# Wifi_and_Tip_120.net
KiCad netlist of a schematic drawn in EAGLE
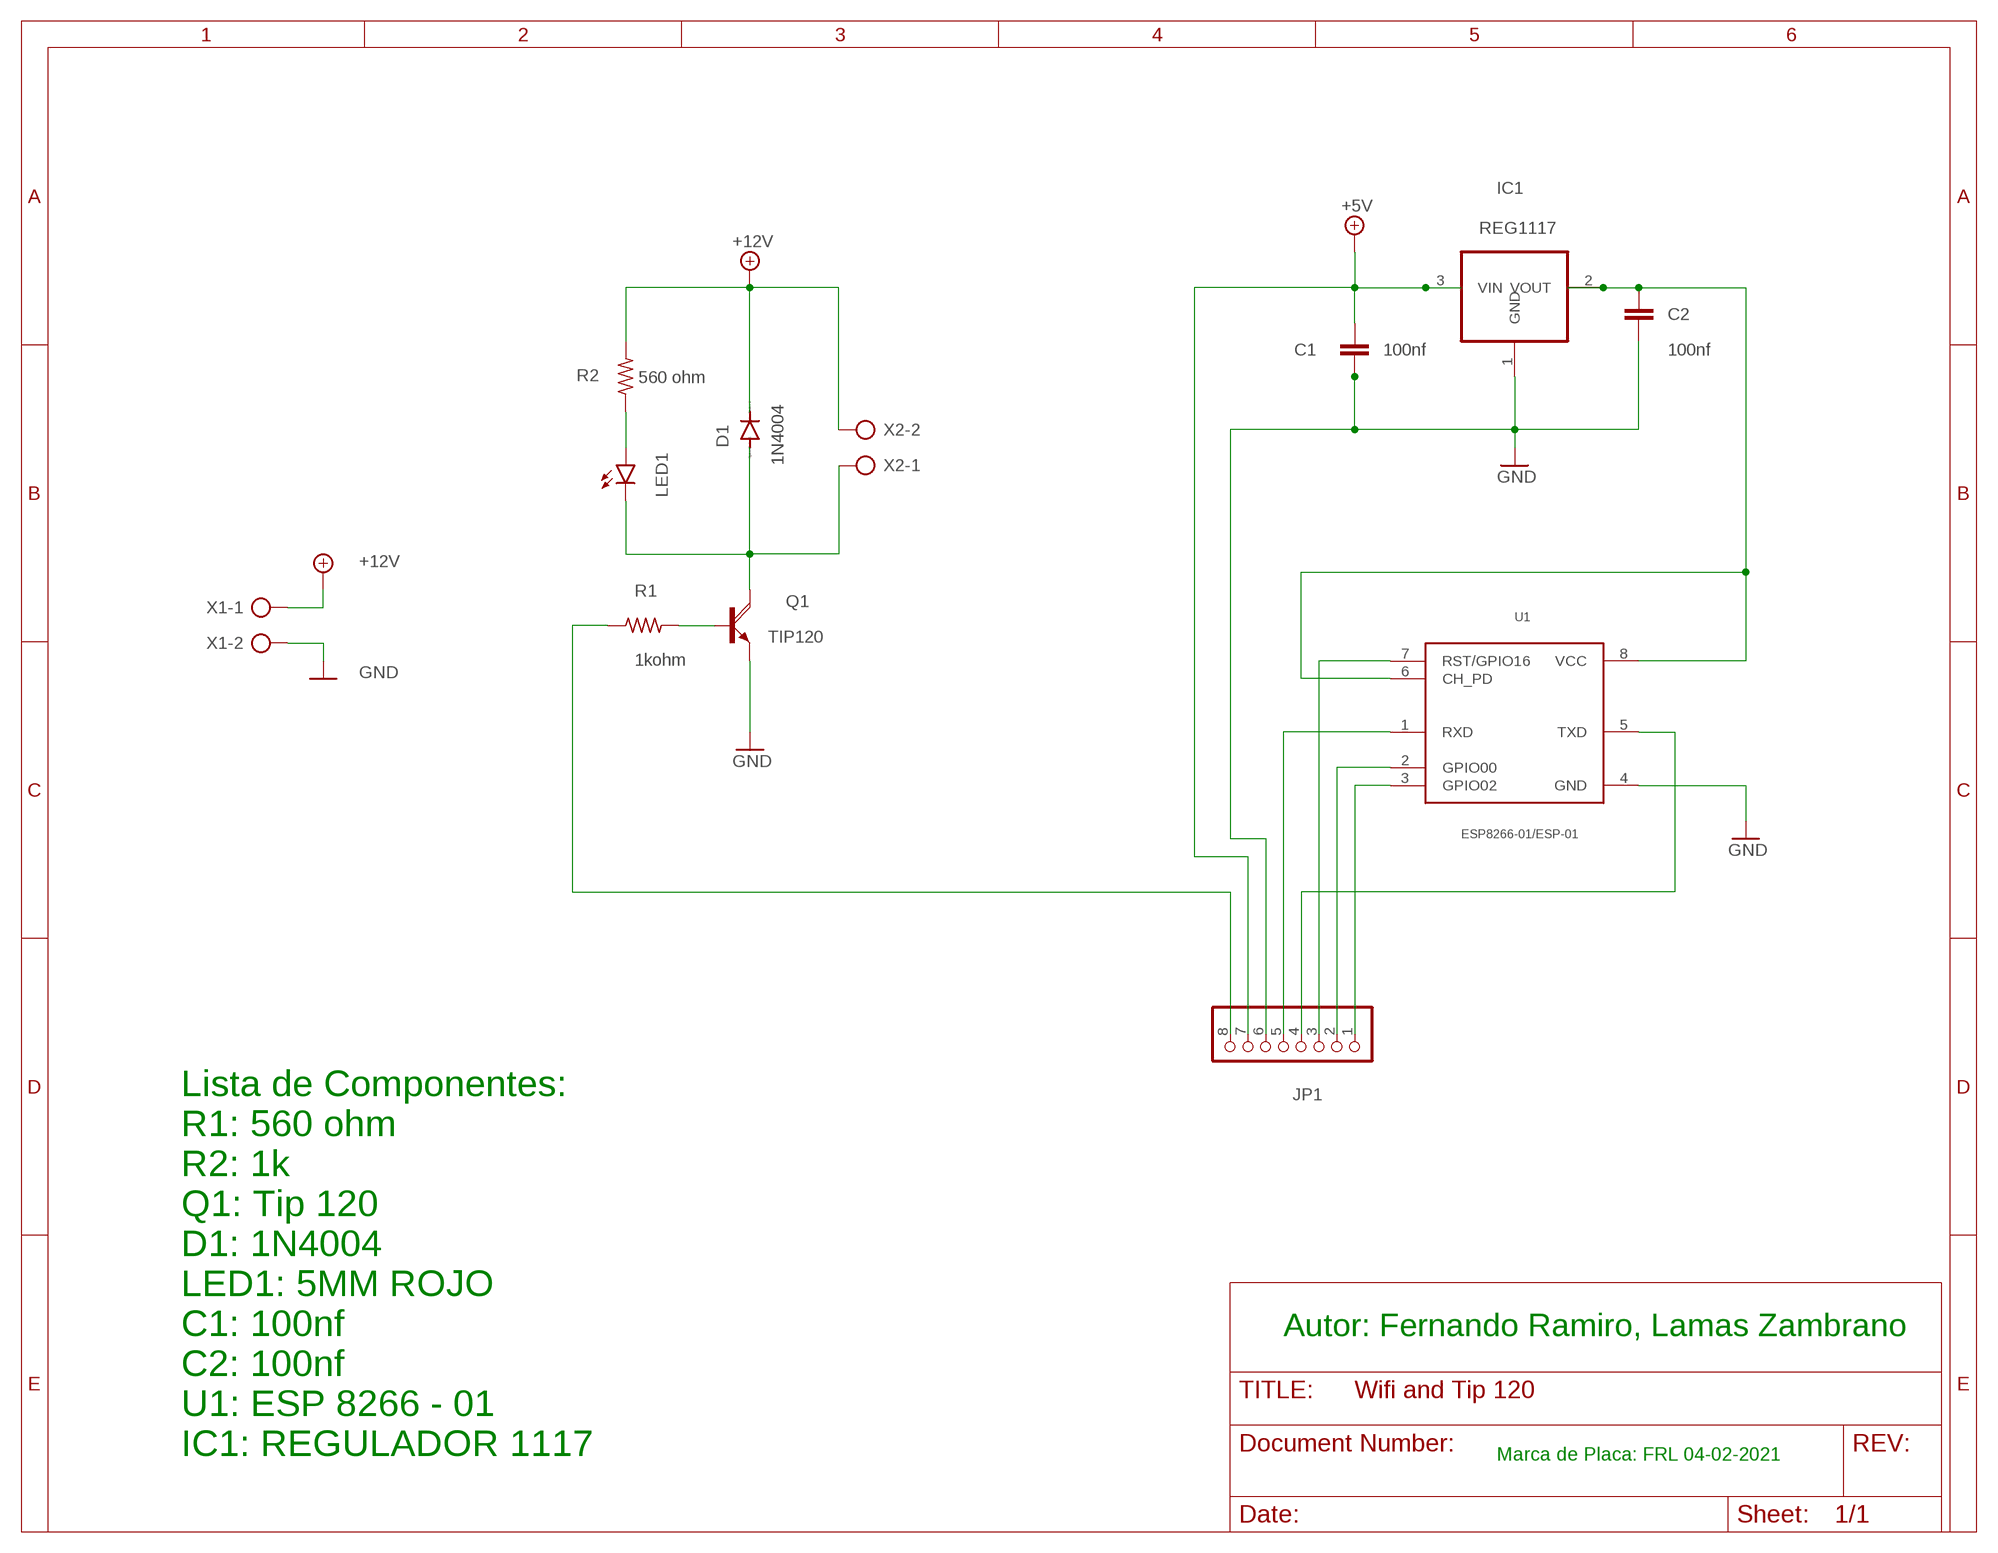
[diagram p0: schematic, sheet 1]

(export (version "E")
  (design (tool "Eeschema 10.0.6"))
  (components
    (comp (ref "C1")
      (value "100nf")
      (footprint "eagle-import:C025-024X044")
      (libsource (lib "eagle-import") (part "C-EU025-024X044"))
    )
    (comp (ref "C2")
      (value "100nf")
      (footprint "eagle-import:C025-024X044")
      (libsource (lib "eagle-import") (part "C-EU025-024X044"))
    )
    (comp (ref "D1")
      (value "1N4004")
      (footprint "eagle-import:DO41-10")
      (libsource (lib "eagle-import") (part "1N4004"))
    )
    (comp (ref "IC1")
      (value "REG1117")
      (footprint "eagle-import:SOT223")
      (libsource (lib "eagle-import") (part "REG1117"))
    )
    (comp (ref "JP1")
      (value "PINHD-1X8")
      (footprint "eagle-import:1X08")
      (libsource (lib "eagle-import") (part "PINHD-1X8"))
    )
    (comp (ref "LED1")
      (value "LED5MM")
      (footprint "eagle-import:LED5MM")
      (libsource (lib "eagle-import") (part "LED5MM"))
    )
    (comp (ref "Q1")
      (value "TIP120")
      (footprint "eagle-import:TO220AH")
      (libsource (lib "eagle-import") (part "TIP120"))
    )
    (comp (ref "R1")
      (value "1kohm")
      (footprint "eagle-import:0207_10")
      (libsource (lib "eagle-import") (part "R-US_0207/10"))
    )
    (comp (ref "R2")
      (value "560 ohm")
      (footprint "eagle-import:0207_10")
      (libsource (lib "eagle-import") (part "R-US_0207/10"))
    )
    (comp (ref "U1")
      (value "ESP8266-01/ESP-01")
      (footprint "eagle-import:XCVR_ESP8266-01_ESP-01")
      (fields (field (name "MF") "AI-Thinker"))
      (libsource (lib "eagle-import") (part "ESP8266-01/ESP-01"))
    )
    (comp (ref "X1")
      (value "AK500/2")
      (footprint "eagle-import:AK500_2")
      (libsource (lib "eagle-import") (part "AK500/2"))
    )
    (comp (ref "X2")
      (value "AK500/2")
      (footprint "eagle-import:AK500_2")
      (libsource (lib "eagle-import") (part "AK500/2"))
    )
  )
  (nets
    (net (code "1") (name "+5V") (class "Default")
      (node (ref "C1") (pin "1") (pinfunction "1_1") (pintype "passive"))
      (node (ref "IC1") (pin "3") (pinfunction "VIN_3") (pintype "input"))
      (node (ref "JP1") (pin "7") (pinfunction "7_7") (pintype "passive"))
    )
    (net (code "2") (name "+12V") (class "Default")
      (node (ref "D1") (pin "C") (pinfunction "C_C") (pintype "passive"))
      (node (ref "R2") (pin "2") (pinfunction "2_2") (pintype "passive"))
      (node (ref "X1") (pin "1") (pinfunction "KL_1") (pintype "passive"))
      (node (ref "X2") (pin "2") (pinfunction "KL_2") (pintype "passive"))
    )
    (net (code "3") (name "GND") (class "Default")
      (node (ref "C1") (pin "2") (pinfunction "2_2") (pintype "passive"))
      (node (ref "C2") (pin "2") (pinfunction "2_2") (pintype "passive"))
      (node (ref "IC1") (pin "1") (pinfunction "GND_1") (pintype "power_in"))
      (node (ref "JP1") (pin "6") (pinfunction "6_6") (pintype "passive"))
      (node (ref "Q1") (pin "E") (pinfunction "E_E") (pintype "passive"))
      (node (ref "U1") (pin "4") (pinfunction "GND_4") (pintype "power_in"))
      (node (ref "X1") (pin "2") (pinfunction "KL_2") (pintype "passive"))
    )
    (net (code "4") (name "Net-(IC1-VOUT)") (class "Default")
      (node (ref "C2") (pin "1") (pinfunction "1_1") (pintype "passive"))
      (node (ref "IC1") (pin "2") (pinfunction "VOUT_2") (pintype "output"))
      (node (ref "U1") (pin "6") (pinfunction "CH_PD_6") (pintype "input"))
      (node (ref "U1") (pin "8") (pinfunction "VCC_8") (pintype "power_in"))
    )
    (net (code "5") (name "Net-(JP1-Pad8)") (class "Default")
      (node (ref "JP1") (pin "8") (pinfunction "8_8") (pintype "passive"))
      (node (ref "R1") (pin "1") (pinfunction "1_1") (pintype "passive"))
    )
    (net (code "6") (name "Net-(LED1-C)") (class "Default")
      (node (ref "D1") (pin "A") (pinfunction "A_A") (pintype "passive"))
      (node (ref "LED1") (pin "K") (pinfunction "C_K") (pintype "passive"))
      (node (ref "Q1") (pin "C") (pinfunction "C_C") (pintype "passive"))
      (node (ref "X2") (pin "1") (pinfunction "KL_1") (pintype "passive"))
    )
    (net (code "7") (name "Net-(LED1-PadA)") (class "Default")
      (node (ref "LED1") (pin "A") (pinfunction "A_A") (pintype "passive"))
      (node (ref "R2") (pin "1") (pinfunction "1_1") (pintype "passive"))
    )
    (net (code "8") (name "Net-(Q1-PadB)") (class "Default")
      (node (ref "Q1") (pin "B") (pinfunction "B_B") (pintype "passive"))
      (node (ref "R1") (pin "2") (pinfunction "2_2") (pintype "passive"))
    )
    (net (code "9") (name "Net-(U1-GPIO00)") (class "Default")
      (node (ref "JP1") (pin "2") (pinfunction "2_2") (pintype "passive"))
      (node (ref "U1") (pin "2") (pinfunction "GPIO00_2") (pintype "bidirectional"))
    )
    (net (code "10") (name "Net-(U1-GPIO02)") (class "Default")
      (node (ref "JP1") (pin "1") (pinfunction "1_1") (pintype "passive"))
      (node (ref "U1") (pin "3") (pinfunction "GPIO02_3") (pintype "bidirectional"))
    )
    (net (code "11") (name "Net-(U1-RST{slash}GPIO16)") (class "Default")
      (node (ref "JP1") (pin "3") (pinfunction "3_3") (pintype "passive"))
      (node (ref "U1") (pin "7") (pinfunction "RST/GPIO16_7") (pintype "input"))
    )
    (net (code "12") (name "Net-(U1-RXD)") (class "Default")
      (node (ref "JP1") (pin "5") (pinfunction "5_5") (pintype "passive"))
      (node (ref "U1") (pin "1") (pinfunction "RXD_1") (pintype "input"))
    )
    (net (code "13") (name "Net-(U1-TXD)") (class "Default")
      (node (ref "JP1") (pin "4") (pinfunction "4_4") (pintype "passive"))
      (node (ref "U1") (pin "5") (pinfunction "TXD_5") (pintype "output"))
    )
  )
)
